# TwoArmedBandit_v1.net
KiCad netlist of a schematic drawn in EAGLE
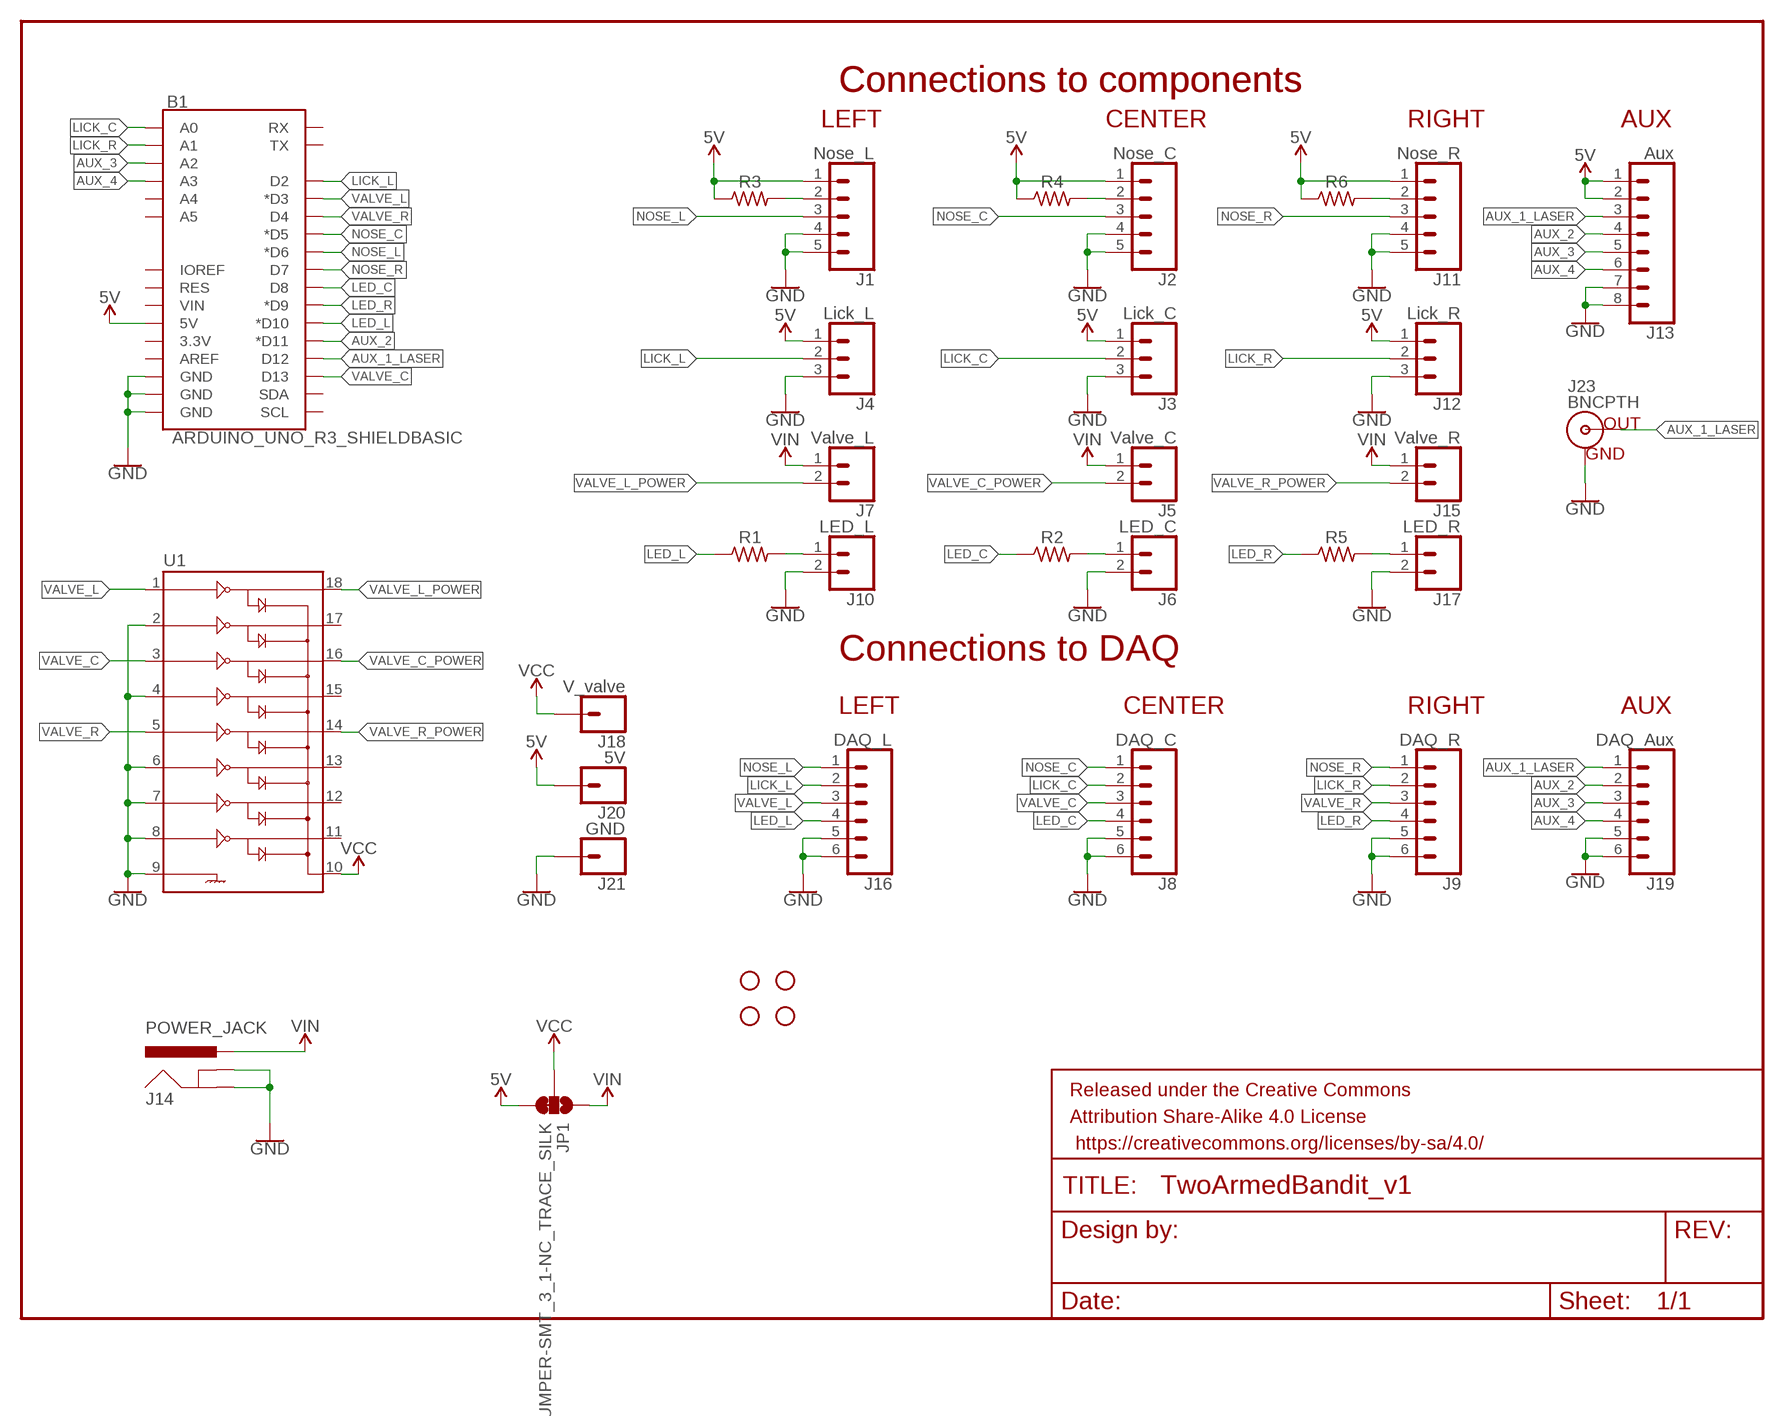
[diagram p0: schematic, sheet 1]

(export (version "E")
  (design (tool "Eeschema 10.0.6"))
  (components
    (comp (ref "B1")
      (value "ARDUINO_UNO_R3_SHIELDBASIC")
      (footprint "eagle-import:UNO_R3_SHIELD")
      (libsource (lib "eagle-import") (part "ARDUINO_UNO_R3_SHIELDBASIC"))
    )
    (comp (ref "FRAME1")
      (value "FRAME-LETTERNO_PACKAGE")
      (footprint "eagle-import:DUMMY")
      (fields (field (name "DESIGNER") "Nobody"))
      (libsource (lib "eagle-import") (part "FRAME-LETTERNO_PACKAGE"))
    )
    (comp (ref "H1")
      (value "STAND-OFF")
      (footprint "eagle-import:STAND-OFF")
      (libsource (lib "eagle-import") (part "STAND-OFF"))
    )
    (comp (ref "H2")
      (value "STAND-OFF")
      (footprint "eagle-import:STAND-OFF")
      (libsource (lib "eagle-import") (part "STAND-OFF"))
    )
    (comp (ref "H3")
      (value "STAND-OFF")
      (footprint "eagle-import:STAND-OFF")
      (libsource (lib "eagle-import") (part "STAND-OFF"))
    )
    (comp (ref "H4")
      (value "STAND-OFF")
      (footprint "eagle-import:STAND-OFF")
      (libsource (lib "eagle-import") (part "STAND-OFF"))
    )
    (comp (ref "J1")
      (value "Nose_L")
      (footprint "eagle-import:SCREWTERMINAL-3.5MM-5")
      (libsource (lib "eagle-import") (part "CONN_05SCREW"))
    )
    (comp (ref "J2")
      (value "Nose_C")
      (footprint "eagle-import:SCREWTERMINAL-3.5MM-5")
      (libsource (lib "eagle-import") (part "CONN_05SCREW"))
    )
    (comp (ref "J3")
      (value "Lick_C")
      (footprint "eagle-import:1X03")
      (libsource (lib "eagle-import") (part "CONN_03"))
    )
    (comp (ref "J4")
      (value "Lick_L")
      (footprint "eagle-import:1X03")
      (libsource (lib "eagle-import") (part "CONN_03"))
    )
    (comp (ref "J5")
      (value "Valve_C")
      (footprint "eagle-import:1X02")
      (libsource (lib "eagle-import") (part "CONN_02"))
    )
    (comp (ref "J6")
      (value "LED_C")
      (footprint "eagle-import:1X02")
      (libsource (lib "eagle-import") (part "CONN_02"))
    )
    (comp (ref "J7")
      (value "Valve_L")
      (footprint "eagle-import:1X02")
      (libsource (lib "eagle-import") (part "CONN_02"))
    )
    (comp (ref "J8")
      (value "DAQ_C")
      (footprint "eagle-import:SCREWTERMINAL-3.5MM-6")
      (libsource (lib "eagle-import") (part "CONN_063.5MM-6"))
    )
    (comp (ref "J9")
      (value "DAQ_R")
      (footprint "eagle-import:SCREWTERMINAL-3.5MM-6")
      (libsource (lib "eagle-import") (part "CONN_063.5MM-6"))
    )
    (comp (ref "J10")
      (value "LED_L")
      (footprint "eagle-import:1X02")
      (libsource (lib "eagle-import") (part "CONN_02"))
    )
    (comp (ref "J11")
      (value "Nose_R")
      (footprint "eagle-import:SCREWTERMINAL-3.5MM-5")
      (libsource (lib "eagle-import") (part "CONN_05SCREW"))
    )
    (comp (ref "J12")
      (value "Lick_R")
      (footprint "eagle-import:1X03")
      (libsource (lib "eagle-import") (part "CONN_03"))
    )
    (comp (ref "J13")
      (value "Aux")
      (footprint "eagle-import:1X08")
      (libsource (lib "eagle-import") (part "CONN_08{dblquote}"))
    )
    (comp (ref "J14")
      (value "POWER_JACK")
      (footprint "eagle-import:POWER_JACK_PTH")
      (libsource (lib "eagle-import") (part "POWER_JACK"))
    )
    (comp (ref "J15")
      (value "Valve_R")
      (footprint "eagle-import:1X02")
      (libsource (lib "eagle-import") (part "CONN_02"))
    )
    (comp (ref "J16")
      (value "DAQ_L")
      (footprint "eagle-import:SCREWTERMINAL-3.5MM-6")
      (libsource (lib "eagle-import") (part "CONN_063.5MM-6"))
    )
    (comp (ref "J17")
      (value "LED_R")
      (footprint "eagle-import:1X02")
      (libsource (lib "eagle-import") (part "CONN_02"))
    )
    (comp (ref "J18")
      (value "V_valve")
      (footprint "eagle-import:1X01_2MM")
      (libsource (lib "eagle-import") (part "CONN_01PTH_2MM"))
    )
    (comp (ref "J19")
      (value "DAQ_Aux")
      (footprint "eagle-import:SCREWTERMINAL-3.5MM-6")
      (libsource (lib "eagle-import") (part "CONN_063.5MM-6"))
    )
    (comp (ref "J20")
      (value "5V")
      (footprint "eagle-import:1X01_2MM")
      (libsource (lib "eagle-import") (part "CONN_01PTH_2MM"))
    )
    (comp (ref "J21")
      (value "GND")
      (footprint "eagle-import:1X01_2MM")
      (libsource (lib "eagle-import") (part "CONN_01PTH_2MM"))
    )
    (comp (ref "J23")
      (value "BNCPTH")
      (footprint "eagle-import:BNC")
      (libsource (lib "eagle-import") (part "BNCPTH"))
    )
    (comp (ref "JP1")
      (value "JUMPER-SMT_3_1-NC_TRACE_SILK")
      (footprint "eagle-import:SMT-JUMPER_3_1-NC_TRACE_SILK")
      (libsource (lib "eagle-import") (part "JUMPER-SMT_3_1-NC_TRACE_SILK"))
    )
    (comp (ref "R1")
      (value "330")
      (footprint "eagle-import:0309_12")
      (libsource (lib "eagle-import") (part "R-US_0309/12"))
    )
    (comp (ref "R2")
      (value "330")
      (footprint "eagle-import:0309_12")
      (libsource (lib "eagle-import") (part "R-US_0309/12"))
    )
    (comp (ref "R3")
      (value "160")
      (footprint "eagle-import:0309_12")
      (libsource (lib "eagle-import") (part "R-US_0309/12"))
    )
    (comp (ref "R4")
      (value "160")
      (footprint "eagle-import:0309_12")
      (libsource (lib "eagle-import") (part "R-US_0309/12"))
    )
    (comp (ref "R5")
      (value "330")
      (footprint "eagle-import:0309_12")
      (libsource (lib "eagle-import") (part "R-US_0309/12"))
    )
    (comp (ref "R6")
      (value "160")
      (footprint "eagle-import:0309_12")
      (libsource (lib "eagle-import") (part "R-US_0309/12"))
    )
    (comp (ref "U1")
      (value "ULN2803DIP")
      (footprint "eagle-import:DIL18")
      (libsource (lib "eagle-import") (part "ULN2803DIP"))
    )
  )
  (nets
    (net (code "1") (name "5V") (class "Default")
      (node (ref "B1") (pin "5V") (pinfunction "5V_5V") (pintype "bidirectional"))
      (node (ref "J1") (pin "1") (pinfunction "1_1") (pintype "passive"))
      (node (ref "J11") (pin "1") (pinfunction "1_1") (pintype "passive"))
      (node (ref "J12") (pin "1") (pinfunction "1_1") (pintype "passive"))
      (node (ref "J13") (pin "1") (pinfunction "1_1") (pintype "passive"))
      (node (ref "J13") (pin "2") (pinfunction "2_2") (pintype "passive"))
      (node (ref "J2") (pin "1") (pinfunction "1_1") (pintype "passive"))
      (node (ref "J20") (pin "1") (pinfunction "1_1") (pintype "passive"))
      (node (ref "J3") (pin "1") (pinfunction "1_1") (pintype "passive"))
      (node (ref "J4") (pin "1") (pinfunction "1_1") (pintype "passive"))
      (node (ref "JP1") (pin "3") (pinfunction "3_3") (pintype "passive"))
      (node (ref "R3") (pin "1") (pinfunction "1_1") (pintype "passive"))
      (node (ref "R4") (pin "1") (pinfunction "1_1") (pintype "passive"))
      (node (ref "R6") (pin "1") (pinfunction "1_1") (pintype "passive"))
    )
    (net (code "2") (name "AUX_1_LASER") (class "Default")
      (node (ref "B1") (pin "D12") (pinfunction "D12_D12") (pintype "bidirectional"))
      (node (ref "J13") (pin "3") (pinfunction "3_3") (pintype "passive"))
      (node (ref "J19") (pin "1") (pinfunction "1_1") (pintype "passive"))
      (node (ref "J23") (pin "S") (pinfunction "OUT_S") (pintype "bidirectional"))
    )
    (net (code "3") (name "AUX_2") (class "Default")
      (node (ref "B1") (pin "D11") (pinfunction "*D11_D11") (pintype "bidirectional"))
      (node (ref "J13") (pin "4") (pinfunction "4_4") (pintype "passive"))
      (node (ref "J19") (pin "2") (pinfunction "2_2") (pintype "passive"))
    )
    (net (code "4") (name "AUX_3") (class "Default")
      (node (ref "B1") (pin "A2") (pinfunction "A2_A2") (pintype "bidirectional"))
      (node (ref "J13") (pin "5") (pinfunction "5_5") (pintype "passive"))
      (node (ref "J19") (pin "3") (pinfunction "3_3") (pintype "passive"))
    )
    (net (code "5") (name "AUX_4") (class "Default")
      (node (ref "B1") (pin "A3") (pinfunction "A3_A3") (pintype "bidirectional"))
      (node (ref "J13") (pin "6") (pinfunction "6_6") (pintype "passive"))
      (node (ref "J19") (pin "4") (pinfunction "4_4") (pintype "passive"))
    )
    (net (code "6") (name "GND") (class "Default")
      (node (ref "B1") (pin "GND@0") (pinfunction "GND_GND@0") (pintype "bidirectional"))
      (node (ref "B1") (pin "GND@1") (pinfunction "GND_GND@1") (pintype "bidirectional"))
      (node (ref "B1") (pin "GND@2") (pinfunction "GND_GND@2") (pintype "bidirectional"))
      (node (ref "J1") (pin "4") (pinfunction "4_4") (pintype "passive"))
      (node (ref "J1") (pin "5") (pinfunction "5_5") (pintype "passive"))
      (node (ref "J10") (pin "2") (pinfunction "2_2") (pintype "passive"))
      (node (ref "J11") (pin "4") (pinfunction "4_4") (pintype "passive"))
      (node (ref "J11") (pin "5") (pinfunction "5_5") (pintype "passive"))
      (node (ref "J12") (pin "3") (pinfunction "3_3") (pintype "passive"))
      (node (ref "J13") (pin "7") (pinfunction "7_7") (pintype "passive"))
      (node (ref "J13") (pin "8") (pinfunction "8_8") (pintype "passive"))
      (node (ref "J14") (pin "GND") (pinfunction "GND_GND") (pintype "bidirectional"))
      (node (ref "J14") (pin "GNDBREAK") (pinfunction "GNDBREAK_GNDBREAK") (pintype "bidirectional"))
      (node (ref "J16") (pin "5") (pinfunction "5_5") (pintype "passive"))
      (node (ref "J16") (pin "6") (pinfunction "6_6") (pintype "passive"))
      (node (ref "J17") (pin "2") (pinfunction "2_2") (pintype "passive"))
      (node (ref "J19") (pin "5") (pinfunction "5_5") (pintype "passive"))
      (node (ref "J19") (pin "6") (pinfunction "6_6") (pintype "passive"))
      (node (ref "J2") (pin "4") (pinfunction "4_4") (pintype "passive"))
      (node (ref "J2") (pin "5") (pinfunction "5_5") (pintype "passive"))
      (node (ref "J21") (pin "1") (pinfunction "1_1") (pintype "passive"))
      (node (ref "J23") (pin "GND") (pinfunction "GND_GND") (pintype "bidirectional"))
      (node (ref "J3") (pin "3") (pinfunction "3_3") (pintype "passive"))
      (node (ref "J4") (pin "3") (pinfunction "3_3") (pintype "passive"))
      (node (ref "J6") (pin "2") (pinfunction "2_2") (pintype "passive"))
      (node (ref "J8") (pin "5") (pinfunction "5_5") (pintype "passive"))
      (node (ref "J8") (pin "6") (pinfunction "6_6") (pintype "passive"))
      (node (ref "J9") (pin "5") (pinfunction "5_5") (pintype "passive"))
      (node (ref "J9") (pin "6") (pinfunction "6_6") (pintype "passive"))
      (node (ref "U1") (pin "2") (pinfunction "2_2") (pintype "bidirectional"))
      (node (ref "U1") (pin "4") (pinfunction "4_4") (pintype "bidirectional"))
      (node (ref "U1") (pin "6") (pinfunction "6_6") (pintype "bidirectional"))
      (node (ref "U1") (pin "7") (pinfunction "7_7") (pintype "bidirectional"))
      (node (ref "U1") (pin "8") (pinfunction "8_8") (pintype "bidirectional"))
      (node (ref "U1") (pin "9") (pinfunction "9_9") (pintype "bidirectional"))
    )
    (net (code "7") (name "LED_C") (class "Default")
      (node (ref "B1") (pin "D8") (pinfunction "D8_D8") (pintype "bidirectional"))
      (node (ref "J8") (pin "4") (pinfunction "4_4") (pintype "passive"))
      (node (ref "R2") (pin "1") (pinfunction "1_1") (pintype "passive"))
    )
    (net (code "8") (name "LED_L") (class "Default")
      (node (ref "B1") (pin "D10") (pinfunction "*D10_D10") (pintype "bidirectional"))
      (node (ref "J16") (pin "4") (pinfunction "4_4") (pintype "passive"))
      (node (ref "R1") (pin "1") (pinfunction "1_1") (pintype "passive"))
    )
    (net (code "9") (name "LED_R") (class "Default")
      (node (ref "B1") (pin "D9") (pinfunction "*D9_D9") (pintype "bidirectional"))
      (node (ref "J9") (pin "4") (pinfunction "4_4") (pintype "passive"))
      (node (ref "R5") (pin "1") (pinfunction "1_1") (pintype "passive"))
    )
    (net (code "10") (name "LICK_C") (class "Default")
      (node (ref "B1") (pin "A0") (pinfunction "A0_A0") (pintype "bidirectional"))
      (node (ref "J3") (pin "2") (pinfunction "2_2") (pintype "passive"))
      (node (ref "J8") (pin "2") (pinfunction "2_2") (pintype "passive"))
    )
    (net (code "11") (name "LICK_L") (class "Default")
      (node (ref "B1") (pin "D2") (pinfunction "D2_D2") (pintype "bidirectional"))
      (node (ref "J16") (pin "2") (pinfunction "2_2") (pintype "passive"))
      (node (ref "J4") (pin "2") (pinfunction "2_2") (pintype "passive"))
    )
    (net (code "12") (name "LICK_R") (class "Default")
      (node (ref "B1") (pin "A1") (pinfunction "A1_A1") (pintype "bidirectional"))
      (node (ref "J12") (pin "2") (pinfunction "2_2") (pintype "passive"))
      (node (ref "J9") (pin "2") (pinfunction "2_2") (pintype "passive"))
    )
    (net (code "13") (name "NOSE_C") (class "Default")
      (node (ref "B1") (pin "D5") (pinfunction "*D5_D5") (pintype "bidirectional"))
      (node (ref "J2") (pin "3") (pinfunction "3_3") (pintype "passive"))
      (node (ref "J8") (pin "1") (pinfunction "1_1") (pintype "passive"))
    )
    (net (code "14") (name "NOSE_L") (class "Default")
      (node (ref "B1") (pin "D6") (pinfunction "*D6_D6") (pintype "bidirectional"))
      (node (ref "J1") (pin "3") (pinfunction "3_3") (pintype "passive"))
      (node (ref "J16") (pin "1") (pinfunction "1_1") (pintype "passive"))
    )
    (net (code "15") (name "NOSE_R") (class "Default")
      (node (ref "B1") (pin "D7") (pinfunction "D7_D7") (pintype "bidirectional"))
      (node (ref "J11") (pin "3") (pinfunction "3_3") (pintype "passive"))
      (node (ref "J9") (pin "1") (pinfunction "1_1") (pintype "passive"))
    )
    (net (code "16") (name "Net-(J1-Pad2)") (class "Default")
      (node (ref "J1") (pin "2") (pinfunction "2_2") (pintype "passive"))
      (node (ref "R3") (pin "2") (pinfunction "2_2") (pintype "passive"))
    )
    (net (code "17") (name "Net-(J2-Pad2)") (class "Default")
      (node (ref "J2") (pin "2") (pinfunction "2_2") (pintype "passive"))
      (node (ref "R4") (pin "2") (pinfunction "2_2") (pintype "passive"))
    )
    (net (code "18") (name "Net-(J6-Pad1)") (class "Default")
      (node (ref "J6") (pin "1") (pinfunction "1_1") (pintype "passive"))
      (node (ref "R2") (pin "2") (pinfunction "2_2") (pintype "passive"))
    )
    (net (code "19") (name "Net-(J10-Pad1)") (class "Default")
      (node (ref "J10") (pin "1") (pinfunction "1_1") (pintype "passive"))
      (node (ref "R1") (pin "2") (pinfunction "2_2") (pintype "passive"))
    )
    (net (code "20") (name "Net-(J11-Pad2)") (class "Default")
      (node (ref "J11") (pin "2") (pinfunction "2_2") (pintype "passive"))
      (node (ref "R6") (pin "2") (pinfunction "2_2") (pintype "passive"))
    )
    (net (code "21") (name "Net-(J17-Pad1)") (class "Default")
      (node (ref "J17") (pin "1") (pinfunction "1_1") (pintype "passive"))
      (node (ref "R5") (pin "2") (pinfunction "2_2") (pintype "passive"))
    )
    (net (code "22") (name "VALVE_C") (class "Default")
      (node (ref "B1") (pin "D13") (pinfunction "D13_D13") (pintype "bidirectional"))
      (node (ref "J8") (pin "3") (pinfunction "3_3") (pintype "passive"))
      (node (ref "U1") (pin "3") (pinfunction "3_3") (pintype "bidirectional"))
    )
    (net (code "23") (name "VALVE_C_POWER") (class "Default")
      (node (ref "J5") (pin "2") (pinfunction "2_2") (pintype "passive"))
      (node (ref "U1") (pin "16") (pinfunction "16_16") (pintype "bidirectional"))
    )
    (net (code "24") (name "VALVE_L") (class "Default")
      (node (ref "B1") (pin "D3") (pinfunction "*D3_D3") (pintype "bidirectional"))
      (node (ref "J16") (pin "3") (pinfunction "3_3") (pintype "passive"))
      (node (ref "U1") (pin "1") (pinfunction "1_1") (pintype "bidirectional"))
    )
    (net (code "25") (name "VALVE_L_POWER") (class "Default")
      (node (ref "J7") (pin "2") (pinfunction "2_2") (pintype "passive"))
      (node (ref "U1") (pin "18") (pinfunction "18_18") (pintype "bidirectional"))
    )
    (net (code "26") (name "VALVE_R") (class "Default")
      (node (ref "B1") (pin "D4") (pinfunction "D4_D4") (pintype "bidirectional"))
      (node (ref "J9") (pin "3") (pinfunction "3_3") (pintype "passive"))
      (node (ref "U1") (pin "5") (pinfunction "5_5") (pintype "bidirectional"))
    )
    (net (code "27") (name "VALVE_R_POWER") (class "Default")
      (node (ref "J15") (pin "2") (pinfunction "2_2") (pintype "passive"))
      (node (ref "U1") (pin "14") (pinfunction "14_14") (pintype "bidirectional"))
    )
    (net (code "28") (name "VCC") (class "Default")
      (node (ref "J18") (pin "1") (pinfunction "1_1") (pintype "passive"))
      (node (ref "JP1") (pin "2") (pinfunction "2_2") (pintype "passive"))
      (node (ref "U1") (pin "10") (pinfunction "10_10") (pintype "bidirectional"))
    )
    (net (code "29") (name "VIN") (class "Default")
      (node (ref "J14") (pin "PWR") (pinfunction "PWR_PWR") (pintype "bidirectional"))
      (node (ref "J15") (pin "1") (pinfunction "1_1") (pintype "passive"))
      (node (ref "J5") (pin "1") (pinfunction "1_1") (pintype "passive"))
      (node (ref "J7") (pin "1") (pinfunction "1_1") (pintype "passive"))
      (node (ref "JP1") (pin "1") (pinfunction "1_1") (pintype "passive"))
    )
    (net (code "30") (name "unconnected-(B1-Pad3.3V)") (class "Default")
      (node (ref "B1") (pin "3.3V") (pinfunction "3.3V_3.3V") (pintype "bidirectional"))
    )
    (net (code "31") (name "unconnected-(B1-PadA4)") (class "Default")
      (node (ref "B1") (pin "A4") (pinfunction "A4_A4") (pintype "bidirectional"))
    )
    (net (code "32") (name "unconnected-(B1-PadA5)") (class "Default")
      (node (ref "B1") (pin "A5") (pinfunction "A5_A5") (pintype "bidirectional"))
    )
    (net (code "33") (name "unconnected-(B1-PadAREF)") (class "Default")
      (node (ref "B1") (pin "AREF") (pinfunction "AREF_AREF") (pintype "bidirectional"))
    )
    (net (code "34") (name "unconnected-(B1-PadIOREF)") (class "Default")
      (node (ref "B1") (pin "IOREF") (pinfunction "IOREF_IOREF") (pintype "bidirectional"))
    )
    (net (code "35") (name "unconnected-(B1-PadRES)") (class "Default")
      (node (ref "B1") (pin "RES") (pinfunction "RES_RES") (pintype "bidirectional"))
    )
    (net (code "36") (name "unconnected-(B1-PadRX)") (class "Default")
      (node (ref "B1") (pin "RX") (pinfunction "RX_RX") (pintype "bidirectional"))
    )
    (net (code "37") (name "unconnected-(B1-PadSCL)") (class "Default")
      (node (ref "B1") (pin "SCL") (pinfunction "SCL_SCL") (pintype "bidirectional"))
    )
    (net (code "38") (name "unconnected-(B1-PadSDA)") (class "Default")
      (node (ref "B1") (pin "SDA") (pinfunction "SDA_SDA") (pintype "bidirectional"))
    )
    (net (code "39") (name "unconnected-(B1-PadTX)") (class "Default")
      (node (ref "B1") (pin "TX") (pinfunction "TX_TX") (pintype "bidirectional"))
    )
    (net (code "40") (name "unconnected-(B1-PadVIN)") (class "Default")
      (node (ref "B1") (pin "VIN") (pinfunction "VIN_VIN") (pintype "bidirectional"))
    )
    (net (code "41") (name "unconnected-(U1-Pad11)") (class "Default")
      (node (ref "U1") (pin "11") (pinfunction "11_11") (pintype "bidirectional"))
    )
    (net (code "42") (name "unconnected-(U1-Pad12)") (class "Default")
      (node (ref "U1") (pin "12") (pinfunction "12_12") (pintype "bidirectional"))
    )
    (net (code "43") (name "unconnected-(U1-Pad13)") (class "Default")
      (node (ref "U1") (pin "13") (pinfunction "13_13") (pintype "bidirectional"))
    )
    (net (code "44") (name "unconnected-(U1-Pad15)") (class "Default")
      (node (ref "U1") (pin "15") (pinfunction "15_15") (pintype "bidirectional"))
    )
    (net (code "45") (name "unconnected-(U1-Pad17)") (class "Default")
      (node (ref "U1") (pin "17") (pinfunction "17_17") (pintype "bidirectional"))
    )
  )
)
